# AWG_USB_Serial_Quad.net
KiCad netlist of a schematic drawn in Altium Designer
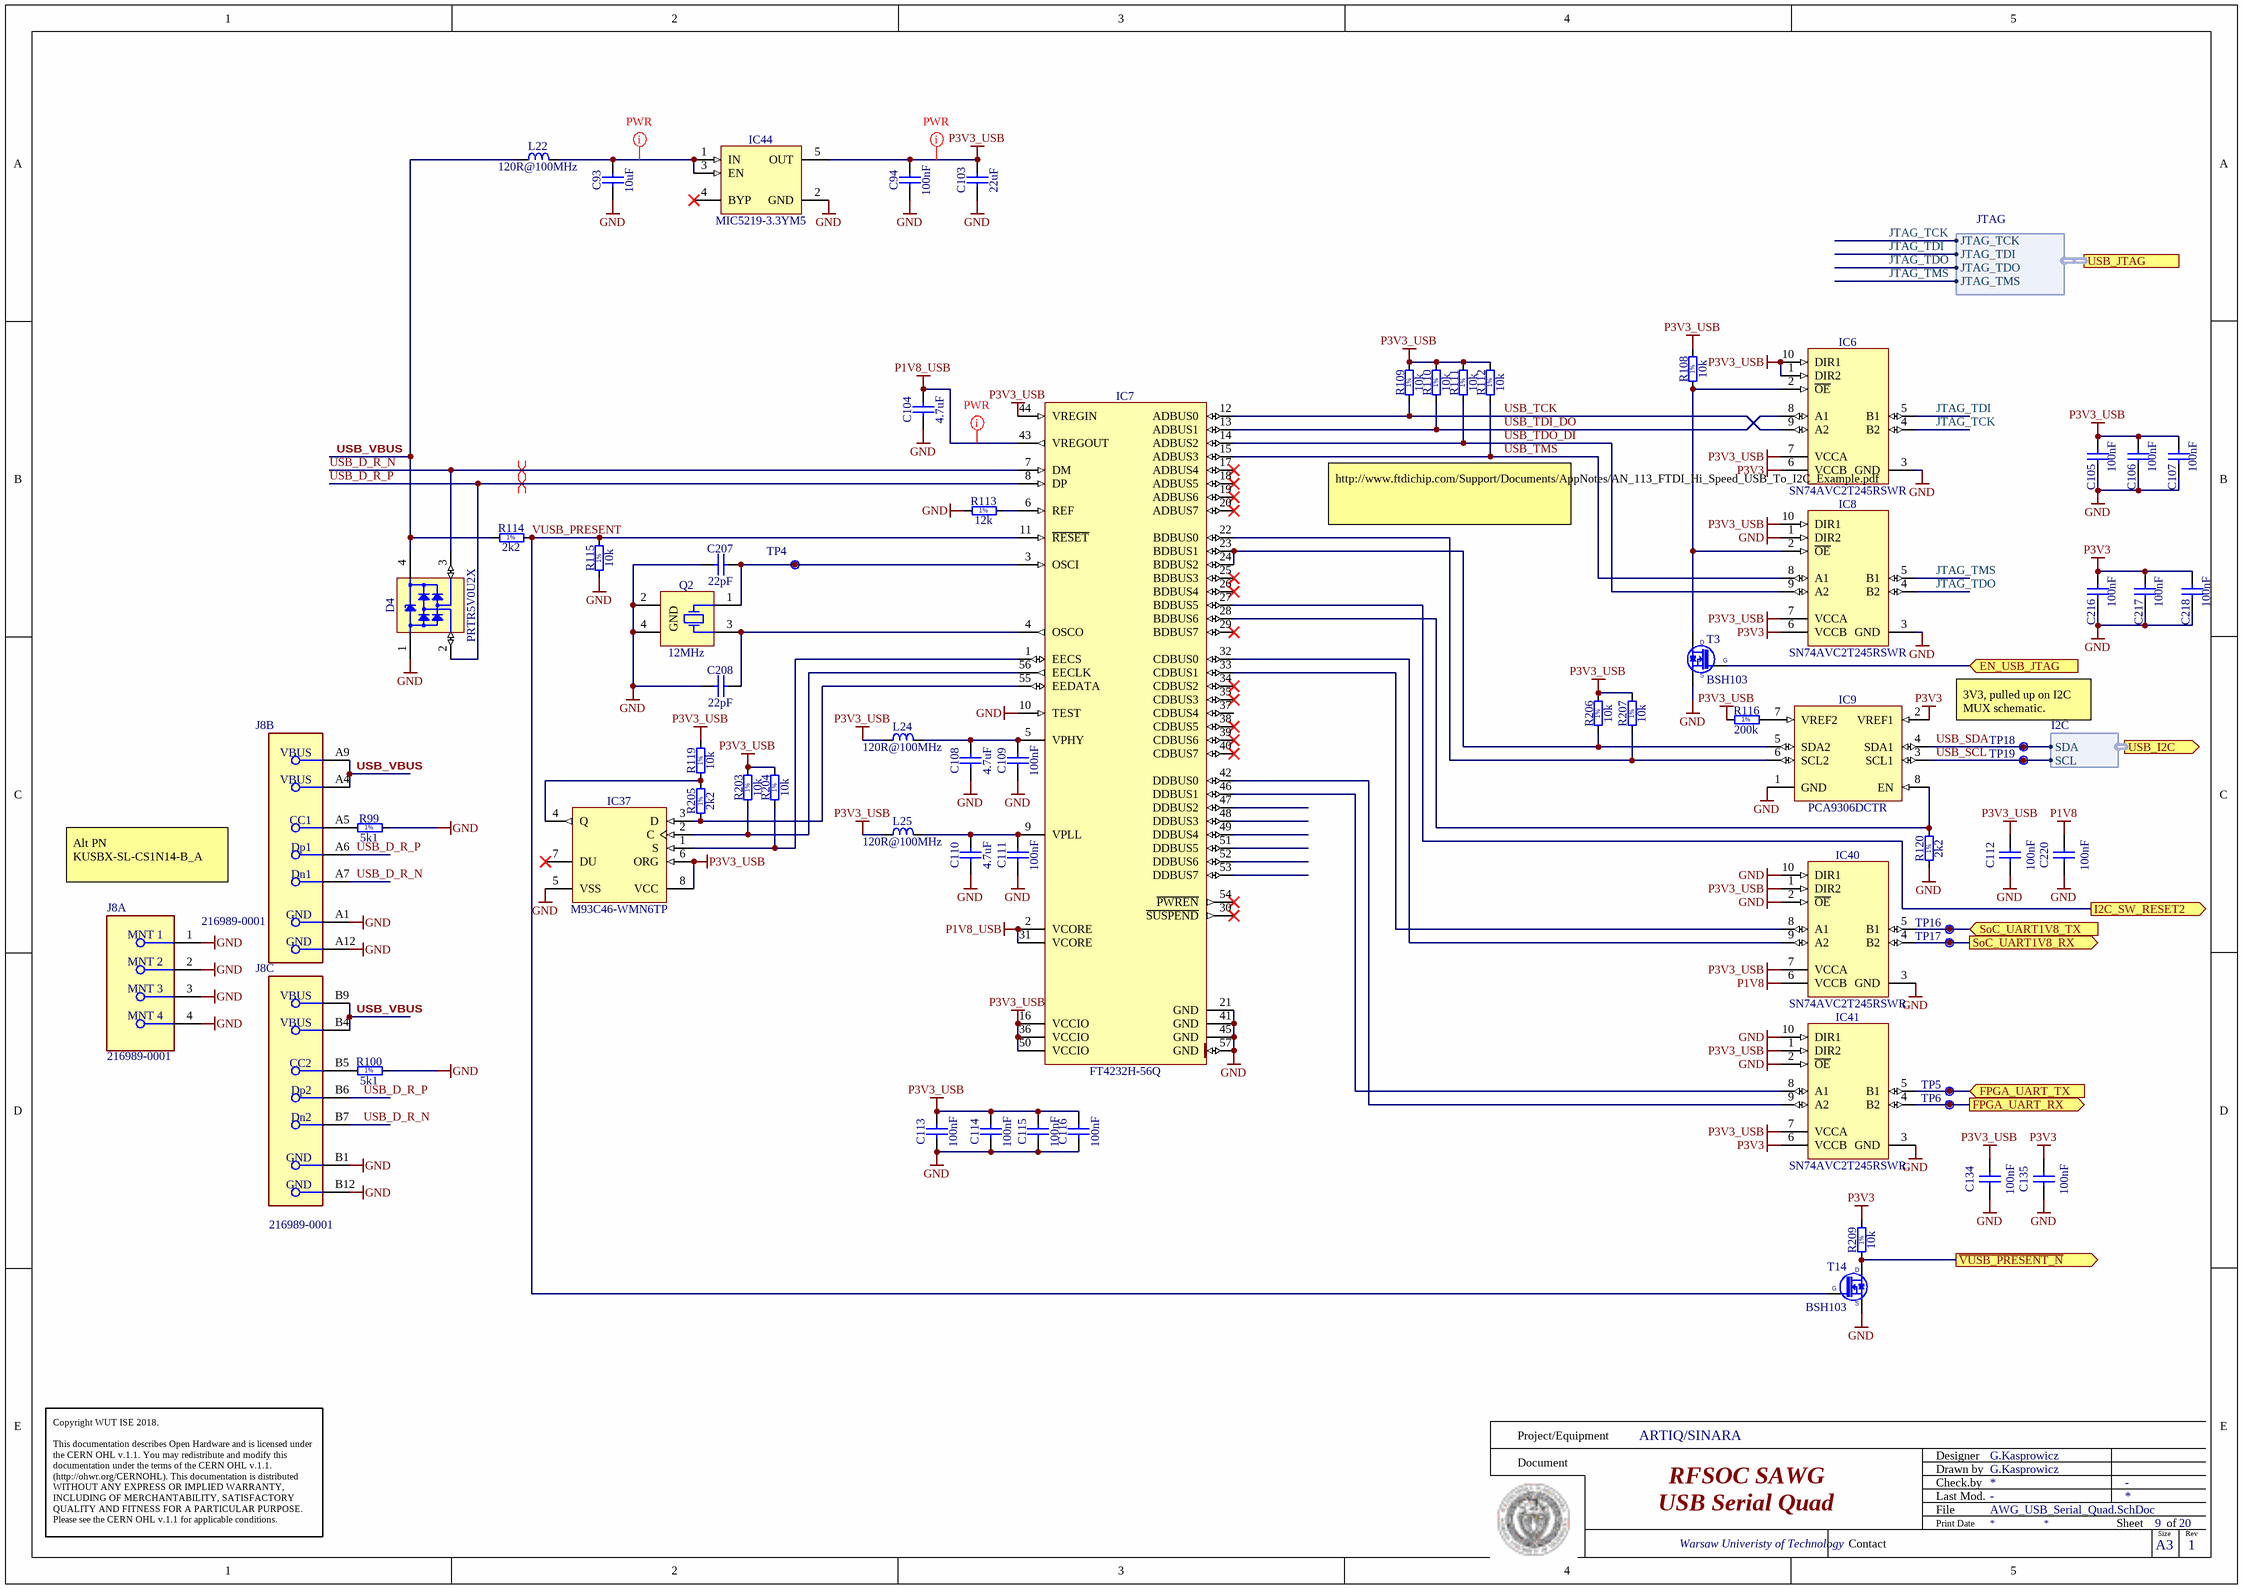
[diagram p0: AWG_USB_Serial_Quad.SchDoc]

(export (version "E")
  (design (tool "Eeschema 10.0.6"))
  (components
    (comp (ref "C93")
      (value "10uF")
      (footprint "CAPC1608X87N")
      (description "Non-polarised capacitor")
      (fields
        (field (name "PART NUMBER") "CC0603_10UF_6.3V_20%_X5R")
        (field (name "VOLTAGE") "6.3V")
        (field (name "AUTHOR") "CERN DEM JLC")
      )
      (libsource (lib "Capacitors") (part "Capacitor - non polarized"))
    )
    (comp (ref "C94")
      (value "100nF")
      (footprint "CAPC1005X55N")
      (description "Non-polarised capacitor")
      (fields
        (field (name "PART NUMBER") "CC0402_100NF_16V_10%_X5R")
        (field (name "VOLTAGE") "16V")
        (field (name "AUTHOR") "CERN DEM JLC")
      )
      (libsource (lib "Capacitors") (part "Capacitor - non polarized"))
    )
    (comp (ref "C103")
      (value "22uF")
      (footprint "CAPC1608X90N")
      (description "Non-polarised capacitor")
      (fields
        (field (name "PART NUMBER") "CC0603_22UF_6.3V_20%_X5R")
        (field (name "VOLTAGE") "6.3V")
        (field (name "AUTHOR") "CERN DEM JLC")
      )
      (libsource (lib "Capacitors") (part "Capacitor - non polarized"))
    )
    (comp (ref "C104")
      (value "4.7uF")
      (footprint "CAPC2012X135N")
      (description "Non-polarised capacitor")
      (fields
        (field (name "PART NUMBER") "CC0805_4.7UF_10V_10%_X5R")
        (field (name "VOLTAGE") "10V")
        (field (name "AUTHOR") "CERN DEM JLC")
      )
      (libsource (lib "Capacitors") (part "Capacitor - non polarized"))
    )
    (comp (ref "C105")
      (value "100nF")
      (footprint "CAPC0603X33N")
      (description "Non-polarised capacitor")
      (fields
        (field (name "PART NUMBER") "CC0201_100NF_6.3V_10%_X5R")
        (field (name "VOLTAGE") "6.3V")
        (field (name "AUTHOR") "CERN DEM JLC")
      )
      (libsource (lib "Capacitors") (part "Capacitor - non polarized"))
    )
    (comp (ref "C106")
      (value "100nF")
      (footprint "CAPC0603X33N")
      (description "Non-polarised capacitor")
      (fields
        (field (name "PART NUMBER") "CC0201_100NF_6.3V_10%_X5R")
        (field (name "VOLTAGE") "6.3V")
        (field (name "AUTHOR") "CERN DEM JLC")
      )
      (libsource (lib "Capacitors") (part "Capacitor - non polarized"))
    )
    (comp (ref "C107")
      (value "100nF")
      (footprint "CAPC0603X33N")
      (description "Non-polarised capacitor")
      (fields
        (field (name "PART NUMBER") "CC0201_100NF_6.3V_10%_X5R")
        (field (name "VOLTAGE") "6.3V")
        (field (name "AUTHOR") "CERN DEM JLC")
      )
      (libsource (lib "Capacitors") (part "Capacitor - non polarized"))
    )
    (comp (ref "C108")
      (value "4.7uF")
      (footprint "CAPC2012X135N")
      (description "Non-polarised capacitor")
      (fields
        (field (name "PART NUMBER") "CC0805_4.7UF_10V_10%_X5R")
        (field (name "VOLTAGE") "10V")
        (field (name "AUTHOR") "CERN DEM JLC")
      )
      (libsource (lib "Capacitors") (part "Capacitor - non polarized"))
    )
    (comp (ref "C109")
      (value "100nF")
      (footprint "CAPC1005X55N")
      (description "Non-polarised capacitor")
      (fields
        (field (name "PART NUMBER") "CC0402_100NF_16V_10%_X5R")
        (field (name "VOLTAGE") "16V")
        (field (name "AUTHOR") "CERN DEM JLC")
      )
      (libsource (lib "Capacitors") (part "Capacitor - non polarized"))
    )
    (comp (ref "C110")
      (value "4.7uF")
      (footprint "CAPC2012X135N")
      (description "Non-polarised capacitor")
      (fields
        (field (name "PART NUMBER") "CC0805_4.7UF_10V_10%_X5R")
        (field (name "VOLTAGE") "10V")
        (field (name "AUTHOR") "CERN DEM JLC")
      )
      (libsource (lib "Capacitors") (part "Capacitor - non polarized"))
    )
    (comp (ref "C111")
      (value "100nF")
      (footprint "CAPC1005X55N")
      (description "Non-polarised capacitor")
      (fields
        (field (name "PART NUMBER") "CC0402_100NF_16V_10%_X5R")
        (field (name "VOLTAGE") "16V")
        (field (name "AUTHOR") "CERN DEM JLC")
      )
      (libsource (lib "Capacitors") (part "Capacitor - non polarized"))
    )
    (comp (ref "C112")
      (value "100nF")
      (footprint "CAPC0603X33N")
      (description "Non-polarised capacitor")
      (fields
        (field (name "PART NUMBER") "CC0201_100NF_6.3V_10%_X5R")
        (field (name "VOLTAGE") "6.3V")
        (field (name "AUTHOR") "CERN DEM JLC")
      )
      (libsource (lib "Capacitors") (part "Capacitor - non polarized"))
    )
    (comp (ref "C113")
      (value "100nF")
      (footprint "CAPC1005X55N")
      (description "Non-polarised capacitor")
      (fields
        (field (name "PART NUMBER") "CC0402_100NF_16V_10%_X5R")
        (field (name "VOLTAGE") "16V")
        (field (name "AUTHOR") "CERN DEM JLC")
      )
      (libsource (lib "Capacitors") (part "Capacitor - non polarized"))
    )
    (comp (ref "C114")
      (value "100nF")
      (footprint "CAPC1005X55N")
      (description "Non-polarised capacitor")
      (fields
        (field (name "PART NUMBER") "CC0402_100NF_16V_10%_X5R")
        (field (name "VOLTAGE") "16V")
        (field (name "AUTHOR") "CERN DEM JLC")
      )
      (libsource (lib "Capacitors") (part "Capacitor - non polarized"))
    )
    (comp (ref "C115")
      (value "100nF")
      (footprint "CAPC1005X55N")
      (description "Non-polarised capacitor")
      (fields
        (field (name "PART NUMBER") "CC0402_100NF_16V_10%_X5R")
        (field (name "VOLTAGE") "16V")
        (field (name "AUTHOR") "CERN DEM JLC")
      )
      (libsource (lib "Capacitors") (part "Capacitor - non polarized"))
    )
    (comp (ref "C116")
      (value "100nF")
      (footprint "CAPC1005X55N")
      (description "Non-polarised capacitor")
      (fields
        (field (name "PART NUMBER") "CC0402_100NF_16V_10%_X5R")
        (field (name "VOLTAGE") "16V")
        (field (name "AUTHOR") "CERN DEM JLC")
      )
      (libsource (lib "Capacitors") (part "Capacitor - non polarized"))
    )
    (comp (ref "C134")
      (value "100nF")
      (footprint "CAPC0603X33N")
      (description "Non-polarised capacitor")
      (fields
        (field (name "PART NUMBER") "CC0201_100NF_6.3V_10%_X5R")
        (field (name "VOLTAGE") "6.3V")
        (field (name "AUTHOR") "CERN DEM JLC")
      )
      (libsource (lib "Capacitors") (part "Capacitor - non polarized"))
    )
    (comp (ref "C135")
      (value "100nF")
      (footprint "CAPC0603X33N")
      (description "Non-polarised capacitor")
      (fields
        (field (name "PART NUMBER") "CC0201_100NF_6.3V_10%_X5R")
        (field (name "VOLTAGE") "6.3V")
        (field (name "AUTHOR") "CERN DEM JLC")
      )
      (libsource (lib "Capacitors") (part "Capacitor - non polarized"))
    )
    (comp (ref "C207")
      (value "22pF")
      (footprint "CAPC1005X55N")
      (description "Non-polarised capacitor")
      (fields
        (field (name "PART NUMBER") "CC0402_22PF_50V_5%_C0G")
        (field (name "VOLTAGE") "50V")
        (field (name "AUTHOR") "CERN DEM JLC")
      )
      (libsource (lib "Capacitors") (part "Capacitor - non polarized"))
    )
    (comp (ref "C208")
      (value "22pF")
      (footprint "CAPC1005X55N")
      (description "Non-polarised capacitor")
      (fields
        (field (name "PART NUMBER") "CC0402_22PF_50V_5%_C0G")
        (field (name "VOLTAGE") "50V")
        (field (name "AUTHOR") "CERN DEM JLC")
      )
      (libsource (lib "Capacitors") (part "Capacitor - non polarized"))
    )
    (comp (ref "C216")
      (value "100nF")
      (footprint "CAPC0603X33N")
      (description "Non-polarised capacitor")
      (fields
        (field (name "PART NUMBER") "CC0201_100NF_6.3V_10%_X5R")
        (field (name "VOLTAGE") "6.3V")
        (field (name "AUTHOR") "CERN DEM JLC")
      )
      (libsource (lib "Capacitors") (part "Capacitor - non polarized"))
    )
    (comp (ref "C217")
      (value "100nF")
      (footprint "CAPC0603X33N")
      (description "Non-polarised capacitor")
      (fields
        (field (name "PART NUMBER") "CC0201_100NF_6.3V_10%_X5R")
        (field (name "VOLTAGE") "6.3V")
        (field (name "AUTHOR") "CERN DEM JLC")
      )
      (libsource (lib "Capacitors") (part "Capacitor - non polarized"))
    )
    (comp (ref "C218")
      (value "100nF")
      (footprint "CAPC0603X33N")
      (description "Non-polarised capacitor")
      (fields
        (field (name "PART NUMBER") "CC0201_100NF_6.3V_10%_X5R")
        (field (name "VOLTAGE") "6.3V")
        (field (name "AUTHOR") "CERN DEM JLC")
      )
      (libsource (lib "Capacitors") (part "Capacitor - non polarized"))
    )
    (comp (ref "C220")
      (value "100nF")
      (footprint "CAPC0603X33N")
      (description "Non-polarised capacitor")
      (fields
        (field (name "PART NUMBER") "CC0201_100NF_6.3V_10%_X5R")
        (field (name "VOLTAGE") "6.3V")
        (field (name "AUTHOR") "CERN DEM JLC")
      )
      (libsource (lib "Capacitors") (part "Capacitor - non polarized"))
    )
    (comp (ref "D4")
      (value "PRTR5V0U2X")
      (footprint "SOT190P230X110-4N")
      (description "Ultra Low Capacitance Double Rail-to-Rail ESD Protection Diode")
      (fields
        (field (name "VOLTAGE") "5.5V")
        (field (name "MANUFACTURER") "NXP SEMICONDUCTORS")
        (field (name "AUTHOR") "CERN DEM JLC")
      )
      (libsource (lib "ICs And Semiconductors") (part "PRTR5V0U2X"))
    )
    (comp (ref "IC6")
      (value "SN74AVC2T245RSWR")
      (footprint "QFN40P140X180X55-10N")
      (description "Dual-Bit Dual-Supply Bus Transceiver With Configurable Voltage Translation and 3-State Outputs")
      (fields (field (name "MANUFACTURER") "TEXAS INSTRUMENTS") (field (name "AUTHOR") "CERN DEM JLC"))
      (libsource (lib "ICs And Semiconductors") (part "742T245"))
    )
    (comp (ref "IC7")
      (value "FT4232H-56Q")
      (footprint "QFN50P800X800X100-57N-S620")
      (description "Quad High Speed USB to Multipurpose UART/MPSSE IC")
      (fields
        (field (name "MANUFACTURER") "FUTURE TECHNOLOGY DEVICES INTERNATIONAL (FTDI)")
        (field (name "AUTHOR") "CERN DEM JLC")
      )
      (libsource (lib "ICs And Semiconductors") (part "FT4232H-56Q"))
    )
    (comp (ref "IC8")
      (value "SN74AVC2T245RSWR")
      (footprint "QFN40P140X180X55-10N")
      (description "Dual-Bit Dual-Supply Bus Transceiver With Configurable Voltage Translation and 3-State Outputs")
      (fields (field (name "MANUFACTURER") "TEXAS INSTRUMENTS") (field (name "AUTHOR") "CERN DEM JLC"))
      (libsource (lib "ICs And Semiconductors") (part "742T245"))
    )
    (comp (ref "IC9")
      (value "PCA9306DCTR")
      (footprint "SOP65P400X130-8N")
      (description "Dual Bidirectional I2C Bus And SMBus Voltage-Level Translator")
      (fields (field (name "MANUFACTURER") "TEXAS INSTRUMENTS") (field (name "AUTHOR") "CERN DEM JLC"))
      (libsource (lib "ICs And Semiconductors") (part "PCA9306D"))
    )
    (comp (ref "IC37")
      (value "M93C46-WMN6TP")
      (footprint "SOIC127P600X175-8N")
      (description "2.5 to 5.5 V, 1Kb (128x8) Serial Microwire Bus EEPROM")
      (fields (field (name "MANUFACTURER") "ST MICROELECTRONICS") (field (name "AUTHOR") "CERN DEM JLC"))
      (libsource (lib "ICs And Semiconductors") (part "M93C46-WMN6TP"))
    )
    (comp (ref "IC40")
      (value "SN74AVC2T245RSWR")
      (footprint "QFN40P140X180X55-10N")
      (description "Dual-Bit Dual-Supply Bus Transceiver With Configurable Voltage Translation and 3-State Outputs")
      (fields (field (name "MANUFACTURER") "TEXAS INSTRUMENTS") (field (name "AUTHOR") "CERN DEM JLC"))
      (libsource (lib "ICs And Semiconductors") (part "742T245"))
    )
    (comp (ref "IC41")
      (value "SN74AVC2T245RSWR")
      (footprint "QFN40P140X180X55-10N")
      (description "Dual-Bit Dual-Supply Bus Transceiver With Configurable Voltage Translation and 3-State Outputs")
      (fields (field (name "MANUFACTURER") "TEXAS INSTRUMENTS") (field (name "AUTHOR") "CERN DEM JLC"))
      (libsource (lib "ICs And Semiconductors") (part "742T245"))
    )
    (comp (ref "IC44")
      (value "MIC5219-3.3YM5")
      (footprint "SOT95P280X145-5N")
      (description "500mA Peak Output LDO Regulator")
      (fields (field (name "MANUFACTURER") "MICROCHIP TECHNOLOGY") (field (name "AUTHOR") "CERN DEM WB"))
      (libsource (lib "ICs And Semiconductors") (part "MIC5219-X.XYM5"))
    )
    (comp (ref "J8")
      (value "216989-0001")
      (footprint "FP-216989-0001-MFG")
      (description "CONN RCPT USB2.0 TYPE C 24POS RA")
      (libsource (lib "Altium Content Vault") (part "0223f526f2db1734dda50670d79969c"))
    )
    (comp (ref "L22")
      (value "120R@100MHz")
      (footprint "INDC1608X65N")
      (description "Inductor")
      (fields
        (field (name "PART NUMBER") "IND0603_MURATA_BLM18SG121TN1D")
        (field (name "POWER") "3A")
        (field (name "AUTHOR") "CERN DEM JLC")
      )
      (libsource (lib "Inductors & Transformers") (part "Inductor"))
    )
    (comp (ref "L24")
      (value "120R@100MHz")
      (footprint "INDC1608X65N")
      (description "Inductor")
      (fields
        (field (name "PART NUMBER") "IND0603_MURATA_BLM18SG121TN1D")
        (field (name "POWER") "3A")
        (field (name "AUTHOR") "CERN DEM JLC")
      )
      (libsource (lib "Inductors & Transformers") (part "Inductor"))
    )
    (comp (ref "L25")
      (value "120R@100MHz")
      (footprint "INDC1608X65N")
      (description "Inductor")
      (fields
        (field (name "PART NUMBER") "IND0603_MURATA_BLM18SG121TN1D")
        (field (name "POWER") "3A")
        (field (name "AUTHOR") "CERN DEM JLC")
      )
      (libsource (lib "Inductors & Transformers") (part "Inductor"))
    )
    (comp (ref "Q2")
      (value "12MHz")
      (footprint "XTAL_TXC_7M")
      (description "Crystal 4 pins 1=XTAL Control 2=GND3=XTAL 4=GND")
      (fields
        (field (name "PART NUMBER") "XTAL_12MHZ_TXC_7M-12.000MAAJ-T")
        (field (name "MANUFACTURER") "TXC CORPORATION")
        (field (name "AUTHOR") "CERN DEM JLC")
      )
      (libsource (lib "ICs And Semiconductors") (part "Quartz Crystal 1X 2GND 3X 4GND"))
    )
    (comp (ref "R99")
      (value "5k1")
      (footprint "RESC1005X40N")
      (description "Resistor - 1%")
      (fields
        (field (name "PART NUMBER") "R0402_5K1_1%_0.0625W_100PPM")
        (field (name "POWER") "0.0625W")
        (field (name "AUTHOR") "CERN DEM JLC")
      )
      (libsource (lib "Resistors") (part "Resistor - 1%"))
    )
    (comp (ref "R100")
      (value "5k1")
      (footprint "RESC1005X40N")
      (description "Resistor - 1%")
      (fields
        (field (name "PART NUMBER") "R0402_5K1_1%_0.0625W_100PPM")
        (field (name "POWER") "0.0625W")
        (field (name "AUTHOR") "CERN DEM JLC")
      )
      (libsource (lib "Resistors") (part "Resistor - 1%"))
    )
    (comp (ref "R108")
      (value "10k")
      (footprint "RESC1005X40N")
      (description "Resistor - 1%")
      (fields
        (field (name "PART NUMBER") "R0402_10K_1%_0.0625W_100PPM")
        (field (name "POWER") "0.0625W")
        (field (name "AUTHOR") "CERN DEM JLC")
      )
      (libsource (lib "Resistors") (part "Resistor - 1%"))
    )
    (comp (ref "R109")
      (value "10k")
      (footprint "RESC1005X40N")
      (description "Resistor - 1%")
      (fields
        (field (name "PART NUMBER") "R0402_10K_1%_0.0625W_100PPM")
        (field (name "POWER") "0.0625W")
        (field (name "AUTHOR") "CERN DEM JLC")
      )
      (libsource (lib "Resistors") (part "Resistor - 1%"))
    )
    (comp (ref "R110")
      (value "10k")
      (footprint "RESC1005X40N")
      (description "Resistor - 1%")
      (fields
        (field (name "PART NUMBER") "R0402_10K_1%_0.0625W_100PPM")
        (field (name "POWER") "0.0625W")
        (field (name "AUTHOR") "CERN DEM JLC")
      )
      (libsource (lib "Resistors") (part "Resistor - 1%"))
    )
    (comp (ref "R111")
      (value "10k")
      (footprint "RESC1005X40N")
      (description "Resistor - 1%")
      (fields
        (field (name "PART NUMBER") "R0402_10K_1%_0.0625W_100PPM")
        (field (name "POWER") "0.0625W")
        (field (name "AUTHOR") "CERN DEM JLC")
      )
      (libsource (lib "Resistors") (part "Resistor - 1%"))
    )
    (comp (ref "R112")
      (value "10k")
      (footprint "RESC1005X40N")
      (description "Resistor - 1%")
      (fields
        (field (name "PART NUMBER") "R0402_10K_1%_0.0625W_100PPM")
        (field (name "POWER") "0.0625W")
        (field (name "AUTHOR") "CERN DEM JLC")
      )
      (libsource (lib "Resistors") (part "Resistor - 1%"))
    )
    (comp (ref "R113")
      (value "12k")
      (footprint "RESC1005X40N")
      (description "Resistor - 1%")
      (fields
        (field (name "PART NUMBER") "R0402_12K_1%_0.0625W_100PPM")
        (field (name "POWER") "0.0625W")
        (field (name "AUTHOR") "CERN DEM JLC")
      )
      (libsource (lib "Resistors") (part "Resistor - 1%"))
    )
    (comp (ref "R114")
      (value "2k2")
      (footprint "RESC1005X40N")
      (description "Resistor - 1%")
      (fields
        (field (name "PART NUMBER") "R0402_2K2_1%_0.0625W_100PPM")
        (field (name "POWER") "0.0625W")
        (field (name "AUTHOR") "CERN DEM JLC")
      )
      (libsource (lib "Resistors") (part "Resistor - 1%"))
    )
    (comp (ref "R115")
      (value "10k")
      (footprint "RESC1005X40N")
      (description "Resistor - 1%")
      (fields
        (field (name "PART NUMBER") "R0402_10K_1%_0.0625W_100PPM")
        (field (name "POWER") "0.0625W")
        (field (name "AUTHOR") "CERN DEM JLC")
      )
      (libsource (lib "Resistors") (part "Resistor - 1%"))
    )
    (comp (ref "R116")
      (value "200k")
      (footprint "RESC1005X40N")
      (description "Resistor - 1%")
      (fields
        (field (name "PART NUMBER") "R0402_200K_1%_0.0625W_100PPM")
        (field (name "POWER") "0.0625W")
        (field (name "AUTHOR") "CERN DEM JLC")
      )
      (libsource (lib "Resistors") (part "Resistor - 1%"))
    )
    (comp (ref "R119")
      (value "10k")
      (footprint "RESC1005X40N")
      (description "Resistor - 1%")
      (fields
        (field (name "PART NUMBER") "R0402_10K_1%_0.0625W_100PPM")
        (field (name "POWER") "0.0625W")
        (field (name "AUTHOR") "CERN DEM JLC")
      )
      (libsource (lib "Resistors") (part "Resistor - 1%"))
    )
    (comp (ref "R120")
      (value "2k2")
      (footprint "RESC1005X40N")
      (description "Resistor - 1%")
      (fields
        (field (name "PART NUMBER") "R0402_2K2_1%_0.0625W_100PPM")
        (field (name "POWER") "0.0625W")
        (field (name "AUTHOR") "CERN DEM JLC")
      )
      (libsource (lib "Resistors") (part "Resistor - 1%"))
    )
    (comp (ref "R203")
      (value "10k")
      (footprint "RESC1005X40N")
      (description "Resistor - 1%")
      (fields
        (field (name "PART NUMBER") "R0402_10K_1%_0.0625W_100PPM")
        (field (name "POWER") "0.0625W")
        (field (name "AUTHOR") "CERN DEM JLC")
      )
      (libsource (lib "Resistors") (part "Resistor - 1%"))
    )
    (comp (ref "R204")
      (value "10k")
      (footprint "RESC1005X40N")
      (description "Resistor - 1%")
      (fields
        (field (name "PART NUMBER") "R0402_10K_1%_0.0625W_100PPM")
        (field (name "POWER") "0.0625W")
        (field (name "AUTHOR") "CERN DEM JLC")
      )
      (libsource (lib "Resistors") (part "Resistor - 1%"))
    )
    (comp (ref "R205")
      (value "2k2")
      (footprint "RESC1005X40N")
      (description "Resistor - 1%")
      (fields
        (field (name "PART NUMBER") "R0402_2K2_1%_0.0625W_100PPM")
        (field (name "POWER") "0.0625W")
        (field (name "AUTHOR") "CERN DEM JLC")
      )
      (libsource (lib "Resistors") (part "Resistor - 1%"))
    )
    (comp (ref "R206")
      (value "10k")
      (footprint "RESC1005X40N")
      (description "Resistor - 1%")
      (fields
        (field (name "PART NUMBER") "R0402_10K_1%_0.0625W_100PPM")
        (field (name "POWER") "0.0625W")
        (field (name "AUTHOR") "CERN DEM JLC")
      )
      (libsource (lib "Resistors") (part "Resistor - 1%"))
    )
    (comp (ref "R207")
      (value "10k")
      (footprint "RESC1005X40N")
      (description "Resistor - 1%")
      (fields
        (field (name "PART NUMBER") "R0402_10K_1%_0.0625W_100PPM")
        (field (name "POWER") "0.0625W")
        (field (name "AUTHOR") "CERN DEM JLC")
      )
      (libsource (lib "Resistors") (part "Resistor - 1%"))
    )
    (comp (ref "R209")
      (value "10k")
      (footprint "RESC1005X40N")
      (description "Resistor - 1%")
      (fields
        (field (name "PART NUMBER") "R0402_10K_1%_0.0625W_100PPM")
        (field (name "POWER") "0.0625W")
        (field (name "AUTHOR") "CERN DEM JLC")
      )
      (libsource (lib "Resistors") (part "Resistor - 1%"))
    )
    (comp (ref "T3")
      (value "BSH103")
      (footprint "SOT95P230X110-3N")
      (description "N-CHANNEL MOSFET WITH DIODE")
      (fields (field (name "MANUFACTURER") "NEXPERIA") (field (name "AUTHOR") "CERN DEM JLC"))
      (libsource (lib "") (part "N-MOSFET-D 1G 2S 3D_1"))
    )
    (comp (ref "T14")
      (value "BSH103")
      (footprint "SOT95P230X110-3N")
      (description "N-CHANNEL MOSFET WITH DIODE")
      (fields (field (name "MANUFACTURER") "NEXPERIA") (field (name "AUTHOR") "CERN DEM JLC"))
      (libsource (lib "ICs And Semiconductors") (part "N-MOSFET-D 1G 2S 3D"))
    )
    (comp (ref "TP4")
      (value "Test Point")
      (footprint "TPS127")
      (fields (field (name "PART NUMBER") "SMD_PAD_1.27X1.27MM") (field (name "AUTHOR") "CERN DEM JLC"))
      (libsource (lib "Eletro-mechanical") (part "Test Point"))
    )
    (comp (ref "TP5")
      (value "Test Point")
      (footprint "TPS127")
      (fields (field (name "PART NUMBER") "SMD_PAD_1.27X1.27MM") (field (name "AUTHOR") "CERN DEM JLC"))
      (libsource (lib "Eletro-mechanical") (part "Test Point"))
    )
    (comp (ref "TP6")
      (value "Test Point")
      (footprint "TPS127")
      (fields (field (name "PART NUMBER") "SMD_PAD_1.27X1.27MM") (field (name "AUTHOR") "CERN DEM JLC"))
      (libsource (lib "Eletro-mechanical") (part "Test Point"))
    )
    (comp (ref "TP16")
      (value "Test Point")
      (footprint "TPS127")
      (fields (field (name "PART NUMBER") "SMD_PAD_1.27X1.27MM") (field (name "AUTHOR") "CERN DEM JLC"))
      (libsource (lib "Eletro-mechanical") (part "Test Point"))
    )
    (comp (ref "TP17")
      (value "Test Point")
      (footprint "TPS127")
      (fields (field (name "PART NUMBER") "SMD_PAD_1.27X1.27MM") (field (name "AUTHOR") "CERN DEM JLC"))
      (libsource (lib "Eletro-mechanical") (part "Test Point"))
    )
    (comp (ref "TP18")
      (value "Test Point")
      (footprint "TPS127")
      (fields (field (name "PART NUMBER") "SMD_PAD_1.27X1.27MM") (field (name "AUTHOR") "CERN DEM JLC"))
      (libsource (lib "Eletro-mechanical") (part "Test Point"))
    )
    (comp (ref "TP19")
      (value "Test Point")
      (footprint "TPS127")
      (fields (field (name "PART NUMBER") "SMD_PAD_1.27X1.27MM") (field (name "AUTHOR") "CERN DEM JLC"))
      (libsource (lib "Eletro-mechanical") (part "Test Point"))
    )
  )
  (nets
    (net (code "3") (name "/EN_USB_JTAG") (class "Default")
      (node (ref "T3") (pin "1") (pinfunction "G_1") (pintype "passive"))
    )
    (net (code "4") (name "/FPGA_UART_RX") (class "Default")
      (node (ref "IC41") (pin "4") (pinfunction "B2_4") (pintype "bidirectional"))
      (node (ref "TP6") (pin "1") (pinfunction "1_1") (pintype "bidirectional"))
    )
    (net (code "5") (name "/FPGA_UART_TX") (class "Default")
      (node (ref "IC41") (pin "5") (pinfunction "B1_5") (pintype "bidirectional"))
      (node (ref "TP5") (pin "1") (pinfunction "1_1") (pintype "bidirectional"))
    )
    (net (code "6") (name "/I2C_SW_RESET2") (class "Default")
      (node (ref "IC7") (pin "27") (pinfunction "BDBUS5_27") (pintype "bidirectional"))
    )
    (net (code "7") (name "/JTAG_TCK") (class "Default")
      (node (ref "IC6") (pin "4") (pinfunction "B2_4") (pintype "bidirectional"))
    )
    (net (code "8") (name "/JTAG_TDI") (class "Default")
      (node (ref "IC6") (pin "5") (pinfunction "B1_5") (pintype "bidirectional"))
    )
    (net (code "9") (name "/JTAG_TDO") (class "Default")
      (node (ref "IC8") (pin "4") (pinfunction "B2_4") (pintype "bidirectional"))
    )
    (net (code "10") (name "/JTAG_TMS") (class "Default")
      (node (ref "IC8") (pin "5") (pinfunction "B1_5") (pintype "bidirectional"))
    )
    (net (code "11") (name "/SoC_UART1V8_RX") (class "Default")
      (node (ref "IC40") (pin "4") (pinfunction "B2_4") (pintype "bidirectional"))
      (node (ref "TP17") (pin "1") (pinfunction "1_1") (pintype "bidirectional"))
    )
    (net (code "12") (name "/SoC_UART1V8_TX") (class "Default")
      (node (ref "IC40") (pin "5") (pinfunction "B1_5") (pintype "bidirectional"))
      (node (ref "TP16") (pin "1") (pinfunction "1_1") (pintype "bidirectional"))
    )
    (net (code "13") (name "/USB_D_R_N") (class "Default")
      (node (ref "D4") (pin "3") (pinfunction "I/O2_3") (pintype "bidirectional"))
      (node (ref "IC7") (pin "7") (pinfunction "DM_7") (pintype "input"))
      (node (ref "J8") (pin "A7") (pinfunction "Dn1_A7") (pintype "passive"))
      (node (ref "J8") (pin "B7") (pinfunction "Dn2_B7") (pintype "passive"))
    )
    (net (code "14") (name "/USB_D_R_P") (class "Default")
      (node (ref "D4") (pin "2") (pinfunction "I/O1_2") (pintype "bidirectional"))
      (node (ref "IC7") (pin "8") (pinfunction "DP_8") (pintype "input"))
      (node (ref "J8") (pin "A6") (pinfunction "Dp1_A6") (pintype "passive"))
      (node (ref "J8") (pin "B6") (pinfunction "Dp2_B6") (pintype "passive"))
    )
    (net (code "15") (name "/USB_SCL") (class "Default")
      (node (ref "IC9") (pin "3") (pinfunction "SCL1_3") (pintype "bidirectional"))
      (node (ref "TP19") (pin "1") (pinfunction "1_1") (pintype "bidirectional"))
    )
    (net (code "16") (name "/USB_SDA") (class "Default")
      (node (ref "IC9") (pin "4") (pinfunction "SDA1_4") (pintype "bidirectional"))
      (node (ref "TP18") (pin "1") (pinfunction "1_1") (pintype "bidirectional"))
    )
    (net (code "17") (name "/USB_TCK") (class "Default")
      (node (ref "IC6") (pin "9") (pinfunction "A2_9") (pintype "bidirectional"))
      (node (ref "IC7") (pin "12") (pinfunction "ADBUS0_12") (pintype "bidirectional"))
      (node (ref "R109") (pin "1") (pinfunction "1_1") (pintype "passive"))
    )
    (net (code "18") (name "/USB_TDI_DO") (class "Default")
      (node (ref "IC6") (pin "8") (pinfunction "A1_8") (pintype "bidirectional"))
      (node (ref "IC7") (pin "13") (pinfunction "ADBUS1_13") (pintype "bidirectional"))
      (node (ref "R110") (pin "1") (pinfunction "1_1") (pintype "passive"))
    )
    (net (code "19") (name "/USB_TDO_DI") (class "Default")
      (node (ref "IC7") (pin "14") (pinfunction "ADBUS2_14") (pintype "bidirectional"))
      (node (ref "IC8") (pin "9") (pinfunction "A2_9") (pintype "bidirectional"))
      (node (ref "R111") (pin "1") (pinfunction "1_1") (pintype "passive"))
    )
    (net (code "20") (name "/USB_TMS") (class "Default")
      (node (ref "IC7") (pin "15") (pinfunction "ADBUS3_15") (pintype "bidirectional"))
      (node (ref "IC8") (pin "8") (pinfunction "A1_8") (pintype "bidirectional"))
      (node (ref "R112") (pin "1") (pinfunction "1_1") (pintype "passive"))
    )
    (net (code "21") (name "/USB_VBUS") (class "Default")
      (node (ref "D4") (pin "4") (pinfunction "VCC_4") (pintype "power_in"))
      (node (ref "J8") (pin "A4") (pinfunction "VBUS_A4") (pintype "passive"))
      (node (ref "J8") (pin "A9") (pinfunction "VBUS_A9") (pintype "power_in"))
      (node (ref "J8") (pin "B4") (pinfunction "VBUS_B4") (pintype "passive"))
      (node (ref "J8") (pin "B9") (pinfunction "VBUS_B9") (pintype "passive"))
      (node (ref "L22") (pin "1") (pinfunction "1_1") (pintype "passive"))
      (node (ref "R114") (pin "1") (pinfunction "1_1") (pintype "passive"))
    )
    (net (code "22") (name "/VUSB_PRESENT") (class "Default")
      (node (ref "IC7") (pin "11") (pinfunction "~{RESET}_11") (pintype "input"))
      (node (ref "R114") (pin "2") (pinfunction "2_2") (pintype "passive"))
      (node (ref "R115") (pin "2") (pinfunction "2_2") (pintype "passive"))
      (node (ref "T14") (pin "1") (pinfunction "G_1") (pintype "passive"))
    )
    (net (code "23") (name "/VUSB_PRESENT_N") (class "Default")
      (node (ref "R209") (pin "1") (pinfunction "1_1") (pintype "passive"))
      (node (ref "T14") (pin "3") (pinfunction "D_3") (pintype "passive"))
    )
    (net (code "26") (name "GND") (class "Default")
      (node (ref "C103") (pin "1") (pinfunction "1_1") (pintype "passive"))
      (node (ref "C104") (pin "1") (pinfunction "1_1") (pintype "passive"))
      (node (ref "C105") (pin "1") (pinfunction "1_1") (pintype "passive"))
      (node (ref "C106") (pin "1") (pinfunction "1_1") (pintype "passive"))
      (node (ref "C107") (pin "1") (pinfunction "1_1") (pintype "passive"))
      (node (ref "C108") (pin "1") (pinfunction "1_1") (pintype "passive"))
      (node (ref "C109") (pin "1") (pinfunction "1_1") (pintype "passive"))
      (node (ref "C110") (pin "1") (pinfunction "1_1") (pintype "passive"))
      (node (ref "C111") (pin "1") (pinfunction "1_1") (pintype "passive"))
      (node (ref "C112") (pin "1") (pinfunction "1_1") (pintype "passive"))
      (node (ref "C113") (pin "1") (pinfunction "1_1") (pintype "passive"))
      (node (ref "C114") (pin "1") (pinfunction "1_1") (pintype "passive"))
      (node (ref "C115") (pin "1") (pinfunction "1_1") (pintype "passive"))
      (node (ref "C116") (pin "1") (pinfunction "1_1") (pintype "passive"))
      (node (ref "C134") (pin "1") (pinfunction "1_1") (pintype "passive"))
      (node (ref "C135") (pin "1") (pinfunction "1_1") (pintype "passive"))
      (node (ref "C207") (pin "1") (pinfunction "1_1") (pintype "passive"))
      (node (ref "C208") (pin "1") (pinfunction "1_1") (pintype "passive"))
      (node (ref "C216") (pin "1") (pinfunction "1_1") (pintype "passive"))
      (node (ref "C217") (pin "1") (pinfunction "1_1") (pintype "passive"))
      (node (ref "C218") (pin "1") (pinfunction "1_1") (pintype "passive"))
      (node (ref "C220") (pin "1") (pinfunction "1_1") (pintype "passive"))
      (node (ref "C93") (pin "1") (pinfunction "1_1") (pintype "passive"))
      (node (ref "C94") (pin "1") (pinfunction "1_1") (pintype "passive"))
      (node (ref "D4") (pin "1") (pinfunction "GND_1") (pintype "power_in"))
      (node (ref "IC37") (pin "5") (pinfunction "VSS_5") (pintype "power_in"))
      (node (ref "IC40") (pin "10") (pinfunction "DIR1_10") (pintype "input"))
      (node (ref "IC40") (pin "2") (pinfunction "~{OE}_2") (pintype "input"))
      (node (ref "IC40") (pin "3") (pinfunction "GND_3") (pintype "power_in"))
      (node (ref "IC41") (pin "10") (pinfunction "DIR1_10") (pintype "input"))
      (node (ref "IC41") (pin "2") (pinfunction "~{OE}_2") (pintype "input"))
      (node (ref "IC41") (pin "3") (pinfunction "GND_3") (pintype "power_in"))
      (node (ref "IC44") (pin "2") (pinfunction "GND_2") (pintype "power_in"))
      (node (ref "IC6") (pin "3") (pinfunction "GND_3") (pintype "power_in"))
      (node (ref "IC7") (pin "10") (pinfunction "TEST_10") (pintype "input"))
      (node (ref "IC7") (pin "21") (pinfunction "GND_21") (pintype "power_in"))
      (node (ref "IC7") (pin "41") (pinfunction "GND_41") (pintype "power_in"))
      (node (ref "IC7") (pin "45") (pinfunction "GND_45") (pintype "power_in"))
      (node (ref "IC7") (pin "57") (pinfunction "GND_57") (pintype "bidirectional"))
      (node (ref "IC8") (pin "1") (pinfunction "DIR2_1") (pintype "input"))
      (node (ref "IC8") (pin "3") (pinfunction "GND_3") (pintype "power_in"))
      (node (ref "IC9") (pin "1") (pinfunction "GND_1") (pintype "power_in"))
      (node (ref "J8") (pin "1") (pinfunction "MNT_1_1") (pintype "passive"))
      (node (ref "J8") (pin "2") (pinfunction "MNT_2_2") (pintype "passive"))
      (node (ref "J8") (pin "3") (pinfunction "MNT_3_3") (pintype "passive"))
      (node (ref "J8") (pin "4") (pinfunction "MNT_4_4") (pintype "passive"))
      (node (ref "J8") (pin "A1") (pinfunction "GND_A1") (pintype "power_in"))
      (node (ref "J8") (pin "A12") (pinfunction "GND_A12") (pintype "power_in"))
      (node (ref "J8") (pin "B1") (pinfunction "GND_B1") (pintype "power_in"))
      (node (ref "J8") (pin "B12") (pinfunction "GND_B12") (pintype "power_in"))
      (node (ref "Q2") (pin "2") (pinfunction "GND_2") (pintype "power_in"))
      (node (ref "Q2") (pin "4") (pinfunction "GND_4") (pintype "power_in"))
      (node (ref "R100") (pin "2") (pinfunction "2_2") (pintype "passive"))
      (node (ref "R113") (pin "1") (pinfunction "1_1") (pintype "passive"))
      (node (ref "R115") (pin "1") (pinfunction "1_1") (pintype "passive"))
      (node (ref "R120") (pin "1") (pinfunction "1_1") (pintype "passive"))
      (node (ref "R99") (pin "2") (pinfunction "2_2") (pintype "passive"))
      (node (ref "T14") (pin "2") (pinfunction "S_2") (pintype "passive"))
      (node (ref "T3") (pin "2") (pinfunction "S_2") (pintype "passive"))
    )
    (net (code "27") (name "Net-(IC6-~{OE})") (class "Default")
      (node (ref "IC6") (pin "2") (pinfunction "~{OE}_2") (pintype "input"))
      (node (ref "IC8") (pin "2") (pinfunction "~{OE}_2") (pintype "input"))
      (node (ref "R108") (pin "1") (pinfunction "1_1") (pintype "passive"))
      (node (ref "T3") (pin "3") (pinfunction "D_3") (pintype "passive"))
    )
    (net (code "28") (name "Net-(IC7-BDBUS0)") (class "Default")
      (node (ref "IC7") (pin "22") (pinfunction "BDBUS0_22") (pintype "bidirectional"))
      (node (ref "IC9") (pin "6") (pinfunction "SCL2_6") (pintype "bidirectional"))
      (node (ref "R207") (pin "1") (pinfunction "1_1") (pintype "passive"))
    )
    (net (code "29") (name "Net-(IC7-BDBUS1)") (class "Default")
      (node (ref "IC7") (pin "23") (pinfunction "BDBUS1_23") (pintype "bidirectional"))
      (node (ref "IC7") (pin "24") (pinfunction "BDBUS2_24") (pintype "bidirectional"))
      (node (ref "IC9") (pin "5") (pinfunction "SDA2_5") (pintype "bidirectional"))
      (node (ref "R206") (pin "1") (pinfunction "1_1") (pintype "passive"))
    )
    (net (code "30") (name "Net-(IC7-BDBUS6)") (class "Default")
      (node (ref "IC7") (pin "28") (pinfunction "BDBUS6_28") (pintype "bidirectional"))
      (node (ref "IC9") (pin "8") (pinfunction "EN_8") (pintype "input"))
      (node (ref "R120") (pin "2") (pinfunction "2_2") (pintype "passive"))
    )
    (net (code "31") (name "Net-(IC7-OSCI)") (class "Default")
      (node (ref "C207") (pin "2") (pinfunction "2_2") (pintype "passive"))
      (node (ref "IC7") (pin "3") (pinfunction "OSCI_3") (pintype "input"))
      (node (ref "Q2") (pin "1") (pinfunction "X_1") (pintype "passive"))
      (node (ref "TP4") (pin "1") (pinfunction "1_1") (pintype "bidirectional"))
    )
    (net (code "32") (name "Net-(IC7-OSCO)") (class "Default")
      (node (ref "C208") (pin "2") (pinfunction "2_2") (pintype "passive"))
      (node (ref "IC7") (pin "4") (pinfunction "OSCO_4") (pintype "output"))
      (node (ref "Q2") (pin "3") (pinfunction "X_3") (pintype "passive"))
    )
    (net (code "33") (name "Net-(IC7-REF)") (class "Default")
      (node (ref "IC7") (pin "6") (pinfunction "REF_6") (pintype "input"))
      (node (ref "R113") (pin "2") (pinfunction "2_2") (pintype "passive"))
    )
    (net (code "34") (name "Net-(IC7-VPHY)") (class "Default")
      (node (ref "C108") (pin "2") (pinfunction "2_2") (pintype "passive"))
      (node (ref "C109") (pin "2") (pinfunction "2_2") (pintype "passive"))
      (node (ref "IC7") (pin "5") (pinfunction "VPHY_5") (pintype "power_in"))
      (node (ref "L24") (pin "2") (pinfunction "2_2") (pintype "passive"))
    )
    (net (code "35") (name "Net-(IC7-VPLL)") (class "Default")
      (node (ref "C110") (pin "2") (pinfunction "2_2") (pintype "passive"))
      (node (ref "C111") (pin "2") (pinfunction "2_2") (pintype "passive"))
      (node (ref "IC7") (pin "9") (pinfunction "VPLL_9") (pintype "power_in"))
      (node (ref "L25") (pin "2") (pinfunction "2_2") (pintype "passive"))
    )
    (net (code "36") (name "Net-(IC9-VREF2)") (class "Default")
      (node (ref "IC9") (pin "7") (pinfunction "VREF2_7") (pintype "input"))
      (node (ref "R116") (pin "2") (pinfunction "2_2") (pintype "passive"))
    )
    (net (code "37") (name "Net-(IC37-C)") (class "Default")
      (node (ref "IC37") (pin "2") (pinfunction "C_2") (pintype "input"))
      (node (ref "IC7") (pin "56") (pinfunction "EECLK_56") (pintype "output"))
      (node (ref "R203") (pin "1") (pinfunction "1_1") (pintype "passive"))
    )
    (net (code "38") (name "Net-(IC37-D)") (class "Default")
      (node (ref "IC37") (pin "3") (pinfunction "D_3") (pintype "input"))
      (node (ref "IC7") (pin "55") (pinfunction "EEDATA_55") (pintype "bidirectional"))
      (node (ref "R205") (pin "2") (pinfunction "2_2") (pintype "passive"))
    )
    (net (code "39") (name "Net-(IC37-Q)") (class "Default")
      (node (ref "IC37") (pin "4") (pinfunction "Q_4") (pintype "output"))
      (node (ref "R119") (pin "1") (pinfunction "1_1") (pintype "passive"))
      (node (ref "R205") (pin "1") (pinfunction "1_1") (pintype "passive"))
    )
    (net (code "40") (name "Net-(IC37-S)") (class "Default")
      (node (ref "IC37") (pin "1") (pinfunction "S_1") (pintype "input"))
      (node (ref "IC7") (pin "1") (pinfunction "EECS_1") (pintype "bidirectional"))
      (node (ref "R204") (pin "1") (pinfunction "1_1") (pintype "passive"))
    )
    (net (code "41") (name "Net-(IC40-A1)") (class "Default")
      (node (ref "IC40") (pin "8") (pinfunction "A1_8") (pintype "bidirectional"))
      (node (ref "IC7") (pin "33") (pinfunction "CDBUS1_33") (pintype "bidirectional"))
    )
    (net (code "42") (name "Net-(IC40-A2)") (class "Default")
      (node (ref "IC40") (pin "9") (pinfunction "A2_9") (pintype "bidirectional"))
      (node (ref "IC7") (pin "32") (pinfunction "CDBUS0_32") (pintype "bidirectional"))
    )
    (net (code "43") (name "Net-(IC41-A1)") (class "Default")
      (node (ref "IC41") (pin "8") (pinfunction "A1_8") (pintype "bidirectional"))
      (node (ref "IC7") (pin "46") (pinfunction "DDBUS1_46") (pintype "bidirectional"))
    )
    (net (code "44") (name "Net-(IC41-A2)") (class "Default")
      (node (ref "IC41") (pin "9") (pinfunction "A2_9") (pintype "bidirectional"))
      (node (ref "IC7") (pin "42") (pinfunction "DDBUS0_42") (pintype "bidirectional"))
    )
    (net (code "45") (name "Net-(IC44-EN)") (class "Default")
      (node (ref "C93") (pin "2") (pinfunction "2_2") (pintype "passive"))
      (node (ref "IC44") (pin "1") (pinfunction "IN_1") (pintype "input"))
      (node (ref "IC44") (pin "3") (pinfunction "EN_3") (pintype "input"))
      (node (ref "L22") (pin "2") (pinfunction "2_2") (pintype "passive"))
    )
    (net (code "46") (name "Net-(J8B-CC1)") (class "Default")
      (node (ref "J8") (pin "A5") (pinfunction "CC1_A5") (pintype "passive"))
      (node (ref "R99") (pin "1") (pinfunction "1_1") (pintype "passive"))
    )
    (net (code "47") (name "Net-(J8C-CC2)") (class "Default")
      (node (ref "J8") (pin "B5") (pinfunction "CC2_B5") (pintype "passive"))
      (node (ref "R100") (pin "1") (pinfunction "1_1") (pintype "passive"))
    )
    (net (code "48") (name "P1V8") (class "Default")
      (node (ref "C220") (pin "2") (pinfunction "2_2") (pintype "passive"))
      (node (ref "IC40") (pin "6") (pinfunction "VCCB_6") (pintype "power_in"))
    )
    (net (code "49") (name "P1V8_USB") (class "Default")
      (node (ref "C104") (pin "2") (pinfunction "2_2") (pintype "passive"))
      (node (ref "IC7") (pin "2") (pinfunction "VCORE_2") (pintype "power_in"))
      (node (ref "IC7") (pin "31") (pinfunction "VCORE_31") (pintype "power_in"))
      (node (ref "IC7") (pin "43") (pinfunction "VREGOUT_43") (pintype "output"))
    )
    (net (code "50") (name "P3V3") (class "Default")
      (node (ref "C135") (pin "2") (pinfunction "2_2") (pintype "passive"))
      (node (ref "C216") (pin "2") (pinfunction "2_2") (pintype "passive"))
      (node (ref "C217") (pin "2") (pinfunction "2_2") (pintype "passive"))
      (node (ref "C218") (pin "2") (pinfunction "2_2") (pintype "passive"))
      (node (ref "IC41") (pin "6") (pinfunction "VCCB_6") (pintype "power_in"))
      (node (ref "IC6") (pin "6") (pinfunction "VCCB_6") (pintype "power_in"))
      (node (ref "IC8") (pin "6") (pinfunction "VCCB_6") (pintype "power_in"))
      (node (ref "IC9") (pin "2") (pinfunction "VREF1_2") (pintype "input"))
      (node (ref "R209") (pin "2") (pinfunction "2_2") (pintype "passive"))
    )
    (net (code "51") (name "P3V3_USB") (class "Default")
      (node (ref "C103") (pin "2") (pinfunction "2_2") (pintype "passive"))
      (node (ref "C105") (pin "2") (pinfunction "2_2") (pintype "passive"))
      (node (ref "C106") (pin "2") (pinfunction "2_2") (pintype "passive"))
      (node (ref "C107") (pin "2") (pinfunction "2_2") (pintype "passive"))
      (node (ref "C112") (pin "2") (pinfunction "2_2") (pintype "passive"))
      (node (ref "C113") (pin "2") (pinfunction "2_2") (pintype "passive"))
      (node (ref "C114") (pin "2") (pinfunction "2_2") (pintype "passive"))
      (node (ref "C115") (pin "2") (pinfunction "2_2") (pintype "passive"))
      (node (ref "C116") (pin "2") (pinfunction "2_2") (pintype "passive"))
      (node (ref "C134") (pin "2") (pinfunction "2_2") (pintype "passive"))
      (node (ref "C94") (pin "2") (pinfunction "2_2") (pintype "passive"))
      (node (ref "IC37") (pin "6") (pinfunction "ORG_6") (pintype "input"))
      (node (ref "IC37") (pin "8") (pinfunction "VCC_8") (pintype "power_in"))
      (node (ref "IC40") (pin "1") (pinfunction "DIR2_1") (pintype "input"))
      (node (ref "IC40") (pin "7") (pinfunction "VCCA_7") (pintype "power_in"))
      (node (ref "IC41") (pin "1") (pinfunction "DIR2_1") (pintype "input"))
      (node (ref "IC41") (pin "7") (pinfunction "VCCA_7") (pintype "power_in"))
      (node (ref "IC44") (pin "5") (pinfunction "OUT_5") (pintype "power_in"))
      (node (ref "IC6") (pin "1") (pinfunction "DIR2_1") (pintype "input"))
      (node (ref "IC6") (pin "10") (pinfunction "DIR1_10") (pintype "input"))
      (node (ref "IC6") (pin "7") (pinfunction "VCCA_7") (pintype "power_in"))
      (node (ref "IC7") (pin "16") (pinfunction "VCCIO_16") (pintype "power_in"))
      (node (ref "IC7") (pin "36") (pinfunction "VCCIO_36") (pintype "power_in"))
      (node (ref "IC7") (pin "44") (pinfunction "VREGIN_44") (pintype "input"))
      (node (ref "IC7") (pin "50") (pinfunction "VCCIO_50") (pintype "power_in"))
      (node (ref "IC8") (pin "10") (pinfunction "DIR1_10") (pintype "input"))
      (node (ref "IC8") (pin "7") (pinfunction "VCCA_7") (pintype "power_in"))
      (node (ref "L24") (pin "1") (pinfunction "1_1") (pintype "passive"))
      (node (ref "L25") (pin "1") (pinfunction "1_1") (pintype "passive"))
      (node (ref "R108") (pin "2") (pinfunction "2_2") (pintype "passive"))
      (node (ref "R109") (pin "2") (pinfunction "2_2") (pintype "passive"))
      (node (ref "R110") (pin "2") (pinfunction "2_2") (pintype "passive"))
      (node (ref "R111") (pin "2") (pinfunction "2_2") (pintype "passive"))
      (node (ref "R112") (pin "2") (pinfunction "2_2") (pintype "passive"))
      (node (ref "R116") (pin "1") (pinfunction "1_1") (pintype "passive"))
      (node (ref "R119") (pin "2") (pinfunction "2_2") (pintype "passive"))
      (node (ref "R203") (pin "2") (pinfunction "2_2") (pintype "passive"))
      (node (ref "R204") (pin "2") (pinfunction "2_2") (pintype "passive"))
      (node (ref "R206") (pin "2") (pinfunction "2_2") (pintype "passive"))
      (node (ref "R207") (pin "2") (pinfunction "2_2") (pintype "passive"))
    )
    (net (code "52") (name "unconnected-(IC7-ADBUS4-Pad17)") (class "Default")
      (node (ref "IC7") (pin "17") (pinfunction "ADBUS4_17") (pintype "bidirectional+no_connect"))
    )
    (net (code "53") (name "unconnected-(IC7-ADBUS5-Pad18)") (class "Default")
      (node (ref "IC7") (pin "18") (pinfunction "ADBUS5_18") (pintype "bidirectional+no_connect"))
    )
    (net (code "54") (name "unconnected-(IC7-ADBUS6-Pad19)") (class "Default")
      (node (ref "IC7") (pin "19") (pinfunction "ADBUS6_19") (pintype "bidirectional+no_connect"))
    )
    (net (code "55") (name "unconnected-(IC7-ADBUS7-Pad20)") (class "Default")
      (node (ref "IC7") (pin "20") (pinfunction "ADBUS7_20") (pintype "bidirectional+no_connect"))
    )
    (net (code "56") (name "unconnected-(IC7-BDBUS3-Pad25)") (class "Default")
      (node (ref "IC7") (pin "25") (pinfunction "BDBUS3_25") (pintype "bidirectional+no_connect"))
    )
    (net (code "57") (name "unconnected-(IC7-BDBUS4-Pad26)") (class "Default")
      (node (ref "IC7") (pin "26") (pinfunction "BDBUS4_26") (pintype "bidirectional+no_connect"))
    )
    (net (code "58") (name "unconnected-(IC7-BDBUS7-Pad29)") (class "Default")
      (node (ref "IC7") (pin "29") (pinfunction "BDBUS7_29") (pintype "bidirectional+no_connect"))
    )
    (net (code "59") (name "unconnected-(IC7-CDBUS2-Pad34)") (class "Default")
      (node (ref "IC7") (pin "34") (pinfunction "CDBUS2_34") (pintype "bidirectional+no_connect"))
    )
    (net (code "60") (name "unconnected-(IC7-CDBUS3-Pad35)") (class "Default")
      (node (ref "IC7") (pin "35") (pinfunction "CDBUS3_35") (pintype "bidirectional+no_connect"))
    )
    (net (code "61") (name "unconnected-(IC7-CDBUS4-Pad37)") (class "Default")
      (node (ref "IC7") (pin "37") (pinfunction "CDBUS4_37") (pintype "bidirectional"))
    )
    (net (code "62") (name "unconnected-(IC7-CDBUS5-Pad38)") (class "Default")
      (node (ref "IC7") (pin "38") (pinfunction "CDBUS5_38") (pintype "bidirectional+no_connect"))
    )
    (net (code "63") (name "unconnected-(IC7-CDBUS6-Pad39)") (class "Default")
      (node (ref "IC7") (pin "39") (pinfunction "CDBUS6_39") (pintype "bidirectional+no_connect"))
    )
    (net (code "64") (name "unconnected-(IC7-CDBUS7-Pad40)") (class "Default")
      (node (ref "IC7") (pin "40") (pinfunction "CDBUS7_40") (pintype "bidirectional+no_connect"))
    )
    (net (code "65") (name "unconnected-(IC7-DDBUS2-Pad47)") (class "Default")
      (node (ref "IC7") (pin "47") (pinfunction "DDBUS2_47") (pintype "bidirectional"))
    )
    (net (code "66") (name "unconnected-(IC7-DDBUS3-Pad48)") (class "Default")
      (node (ref "IC7") (pin "48") (pinfunction "DDBUS3_48") (pintype "bidirectional"))
    )
    (net (code "67") (name "unconnected-(IC7-DDBUS4-Pad49)") (class "Default")
      (node (ref "IC7") (pin "49") (pinfunction "DDBUS4_49") (pintype "bidirectional"))
    )
    (net (code "68") (name "unconnected-(IC7-DDBUS5-Pad51)") (class "Default")
      (node (ref "IC7") (pin "51") (pinfunction "DDBUS5_51") (pintype "bidirectional"))
    )
    (net (code "69") (name "unconnected-(IC7-DDBUS6-Pad52)") (class "Default")
      (node (ref "IC7") (pin "52") (pinfunction "DDBUS6_52") (pintype "bidirectional"))
    )
    (net (code "70") (name "unconnected-(IC7-DDBUS7-Pad53)") (class "Default")
      (node (ref "IC7") (pin "53") (pinfunction "DDBUS7_53") (pintype "bidirectional"))
    )
    (net (code "71") (name "unconnected-(IC7-~{PWREN}-Pad54)") (class "Default")
      (node (ref "IC7") (pin "54") (pinfunction "~{PWREN}_54") (pintype "output+no_connect"))
    )
    (net (code "72") (name "unconnected-(IC7-~{SUSPEND}-Pad30)") (class "Default")
      (node (ref "IC7") (pin "30") (pinfunction "~{SUSPEND}_30") (pintype "output+no_connect"))
    )
    (net (code "73") (name "unconnected-(IC37-DU-Pad7)") (class "Default")
      (node (ref "IC37") (pin "7") (pinfunction "DU_7") (pintype "passive+no_connect"))
    )
    (net (code "74") (name "unconnected-(IC44-BYP-Pad4)") (class "Default")
      (node (ref "IC44") (pin "4") (pinfunction "BYP_4") (pintype "passive+no_connect"))
    )
  )
)
